# sma-test-20190912a.net
KiCad netlist of a schematic drawn in EAGLE
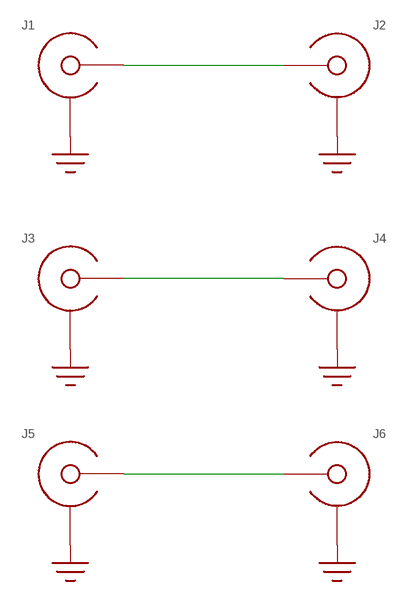
[diagram p0: schematic, sheet 1]

(export (version "E")
  (design (tool "Eeschema 10.0.6"))
  (components
    (comp (ref "J1")
      (value "SMA-EDGE-LAUNCH4020N")
      (footprint "eagle-import:SMA_EDGE_LAUNCH_4L_4020_N")
      (libsource (lib "eagle-import") (part "SMA-EDGE-LAUNCH4020N"))
    )
    (comp (ref "J2")
      (value "SMA-EDGE-LAUNCH4020N1")
      (footprint "eagle-import:SMA_EDGE_LAUNCH_4L_4020_N1")
      (libsource (lib "eagle-import") (part "SMA-EDGE-LAUNCH4020N1"))
    )
    (comp (ref "J3")
      (value "SMA-EDGE-LAUNCH4020N2")
      (footprint "eagle-import:SMA_EDGE_LAUNCH_4L_4020_N2")
      (libsource (lib "eagle-import") (part "SMA-EDGE-LAUNCH4020N2"))
    )
    (comp (ref "J4")
      (value "SMA-EDGE-LAUNCH4020N3")
      (footprint "eagle-import:SMA_EDGE_LAUNCH_4L_4020_N3")
      (libsource (lib "eagle-import") (part "SMA-EDGE-LAUNCH4020N3"))
    )
    (comp (ref "J5")
      (value "SMA-EDGE-LAUNCH4020N4")
      (footprint "eagle-import:SMA_EDGE_LAUNCH_4L_4020_N4")
      (libsource (lib "eagle-import") (part "SMA-EDGE-LAUNCH4020N4"))
    )
    (comp (ref "J6")
      (value "SMA-EDGE-LAUNCH4L-4020-TAPER-FIXED")
      (footprint "eagle-import:SMA_EDGE_LAUNCH_4L_4020_TAPER_FIXED")
      (libsource (lib "eagle-import") (part "SMA-EDGE-LAUNCH4L-4020-TAPER-FIXED"))
    )
  )
  (nets
    (net (code "1") (name "GND") (class "Default")
      (node (ref "J1") (pin "BOTTOM_GND") (pinfunction "SHIELD_BOTTOM_GND") (pintype "bidirectional"))
      (node (ref "J1") (pin "GND@1") (pinfunction "SHIELD_GND@1") (pintype "bidirectional"))
      (node (ref "J1") (pin "GND@14") (pinfunction "SHIELD_GND@14") (pintype "bidirectional"))
      (node (ref "J1") (pin "GND@15") (pinfunction "SHIELD_GND@15") (pintype "bidirectional"))
      (node (ref "J1") (pin "GND@16") (pinfunction "SHIELD_GND@16") (pintype "bidirectional"))
      (node (ref "J1") (pin "GND@17") (pinfunction "SHIELD_GND@17") (pintype "bidirectional"))
      (node (ref "J1") (pin "GND@2") (pinfunction "SHIELD_GND@2") (pintype "bidirectional"))
      (node (ref "J1") (pin "GND@3") (pinfunction "SHIELD_GND@3") (pintype "bidirectional"))
      (node (ref "J1") (pin "GND@4") (pinfunction "SHIELD_GND@4") (pintype "bidirectional"))
      (node (ref "J1") (pin "GND@5") (pinfunction "SHIELD_GND@5") (pintype "bidirectional"))
      (node (ref "J1") (pin "GND@6") (pinfunction "SHIELD_GND@6") (pintype "bidirectional"))
      (node (ref "J1") (pin "GND@7") (pinfunction "SHIELD_GND@7") (pintype "bidirectional"))
      (node (ref "J1") (pin "GND@8") (pinfunction "SHIELD_GND@8") (pintype "bidirectional"))
      (node (ref "J1") (pin "GND_PAD1") (pinfunction "SHIELD_GND_PAD1") (pintype "bidirectional"))
      (node (ref "J1") (pin "GND_PAD2") (pinfunction "SHIELD_GND_PAD2") (pintype "bidirectional"))
      (node (ref "J1") (pin "P$1") (pinfunction "SHIELD_P$1") (pintype "bidirectional"))
      (node (ref "J1") (pin "P$2") (pinfunction "SHIELD_P$2") (pintype "bidirectional"))
      (node (ref "J2") (pin "BOTTOM_GND") (pinfunction "SHIELD_BOTTOM_GND") (pintype "bidirectional"))
      (node (ref "J2") (pin "GND@1") (pinfunction "SHIELD_GND@1") (pintype "bidirectional"))
      (node (ref "J2") (pin "GND@14") (pinfunction "SHIELD_GND@14") (pintype "bidirectional"))
      (node (ref "J2") (pin "GND@15") (pinfunction "SHIELD_GND@15") (pintype "bidirectional"))
      (node (ref "J2") (pin "GND@16") (pinfunction "SHIELD_GND@16") (pintype "bidirectional"))
      (node (ref "J2") (pin "GND@17") (pinfunction "SHIELD_GND@17") (pintype "bidirectional"))
      (node (ref "J2") (pin "GND@2") (pinfunction "SHIELD_GND@2") (pintype "bidirectional"))
      (node (ref "J2") (pin "GND@3") (pinfunction "SHIELD_GND@3") (pintype "bidirectional"))
      (node (ref "J2") (pin "GND@4") (pinfunction "SHIELD_GND@4") (pintype "bidirectional"))
      (node (ref "J2") (pin "GND@5") (pinfunction "SHIELD_GND@5") (pintype "bidirectional"))
      (node (ref "J2") (pin "GND@6") (pinfunction "SHIELD_GND@6") (pintype "bidirectional"))
      (node (ref "J2") (pin "GND@7") (pinfunction "SHIELD_GND@7") (pintype "bidirectional"))
      (node (ref "J2") (pin "GND@8") (pinfunction "SHIELD_GND@8") (pintype "bidirectional"))
      (node (ref "J2") (pin "GND_PAD1") (pinfunction "SHIELD_GND_PAD1") (pintype "bidirectional"))
      (node (ref "J2") (pin "GND_PAD2") (pinfunction "SHIELD_GND_PAD2") (pintype "bidirectional"))
      (node (ref "J2") (pin "P$1") (pinfunction "SHIELD_P$1") (pintype "bidirectional"))
      (node (ref "J2") (pin "P$2") (pinfunction "SHIELD_P$2") (pintype "bidirectional"))
      (node (ref "J2") (pin "P$3") (pinfunction "SHIELD_P$3") (pintype "bidirectional"))
      (node (ref "J2") (pin "P$4") (pinfunction "SHIELD_P$4") (pintype "bidirectional"))
      (node (ref "J2") (pin "P$5") (pinfunction "SHIELD_P$5") (pintype "bidirectional"))
      (node (ref "J3") (pin "BOTTOM_GND") (pinfunction "SHIELD_BOTTOM_GND") (pintype "bidirectional"))
      (node (ref "J3") (pin "GND@1") (pinfunction "SHIELD_GND@1") (pintype "bidirectional"))
      (node (ref "J3") (pin "GND@14") (pinfunction "SHIELD_GND@14") (pintype "bidirectional"))
      (node (ref "J3") (pin "GND@15") (pinfunction "SHIELD_GND@15") (pintype "bidirectional"))
      (node (ref "J3") (pin "GND@16") (pinfunction "SHIELD_GND@16") (pintype "bidirectional"))
      (node (ref "J3") (pin "GND@17") (pinfunction "SHIELD_GND@17") (pintype "bidirectional"))
      (node (ref "J3") (pin "GND@2") (pinfunction "SHIELD_GND@2") (pintype "bidirectional"))
      (node (ref "J3") (pin "GND@3") (pinfunction "SHIELD_GND@3") (pintype "bidirectional"))
      (node (ref "J3") (pin "GND@4") (pinfunction "SHIELD_GND@4") (pintype "bidirectional"))
      (node (ref "J3") (pin "GND@5") (pinfunction "SHIELD_GND@5") (pintype "bidirectional"))
      (node (ref "J3") (pin "GND@6") (pinfunction "SHIELD_GND@6") (pintype "bidirectional"))
      (node (ref "J3") (pin "GND@7") (pinfunction "SHIELD_GND@7") (pintype "bidirectional"))
      (node (ref "J3") (pin "GND@8") (pinfunction "SHIELD_GND@8") (pintype "bidirectional"))
      (node (ref "J3") (pin "GND_PAD1") (pinfunction "SHIELD_GND_PAD1") (pintype "bidirectional"))
      (node (ref "J3") (pin "GND_PAD2") (pinfunction "SHIELD_GND_PAD2") (pintype "bidirectional"))
      (node (ref "J3") (pin "P$1") (pinfunction "SHIELD_P$1") (pintype "bidirectional"))
      (node (ref "J3") (pin "P$2") (pinfunction "SHIELD_P$2") (pintype "bidirectional"))
      (node (ref "J4") (pin "BOTTOM_GND") (pinfunction "SHIELD_BOTTOM_GND") (pintype "bidirectional"))
      (node (ref "J4") (pin "GND@1") (pinfunction "SHIELD_GND@1") (pintype "bidirectional"))
      (node (ref "J4") (pin "GND@14") (pinfunction "SHIELD_GND@14") (pintype "bidirectional"))
      (node (ref "J4") (pin "GND@15") (pinfunction "SHIELD_GND@15") (pintype "bidirectional"))
      (node (ref "J4") (pin "GND@16") (pinfunction "SHIELD_GND@16") (pintype "bidirectional"))
      (node (ref "J4") (pin "GND@17") (pinfunction "SHIELD_GND@17") (pintype "bidirectional"))
      (node (ref "J4") (pin "GND@2") (pinfunction "SHIELD_GND@2") (pintype "bidirectional"))
      (node (ref "J4") (pin "GND@3") (pinfunction "SHIELD_GND@3") (pintype "bidirectional"))
      (node (ref "J4") (pin "GND@4") (pinfunction "SHIELD_GND@4") (pintype "bidirectional"))
      (node (ref "J4") (pin "GND@5") (pinfunction "SHIELD_GND@5") (pintype "bidirectional"))
      (node (ref "J4") (pin "GND@6") (pinfunction "SHIELD_GND@6") (pintype "bidirectional"))
      (node (ref "J4") (pin "GND@7") (pinfunction "SHIELD_GND@7") (pintype "bidirectional"))
      (node (ref "J4") (pin "GND@8") (pinfunction "SHIELD_GND@8") (pintype "bidirectional"))
      (node (ref "J4") (pin "GND_PAD1") (pinfunction "SHIELD_GND_PAD1") (pintype "bidirectional"))
      (node (ref "J4") (pin "GND_PAD2") (pinfunction "SHIELD_GND_PAD2") (pintype "bidirectional"))
      (node (ref "J4") (pin "P$1") (pinfunction "SHIELD_P$1") (pintype "bidirectional"))
      (node (ref "J4") (pin "P$2") (pinfunction "SHIELD_P$2") (pintype "bidirectional"))
      (node (ref "J4") (pin "P$3") (pinfunction "SHIELD_P$3") (pintype "bidirectional"))
      (node (ref "J4") (pin "P$4") (pinfunction "SHIELD_P$4") (pintype "bidirectional"))
      (node (ref "J5") (pin "BOTTOM_GND") (pinfunction "SHIELD_BOTTOM_GND") (pintype "bidirectional"))
      (node (ref "J5") (pin "GND@1") (pinfunction "SHIELD_GND@1") (pintype "bidirectional"))
      (node (ref "J5") (pin "GND@10") (pinfunction "SHIELD_GND@10") (pintype "bidirectional"))
      (node (ref "J5") (pin "GND@14") (pinfunction "SHIELD_GND@14") (pintype "bidirectional"))
      (node (ref "J5") (pin "GND@15") (pinfunction "SHIELD_GND@15") (pintype "bidirectional"))
      (node (ref "J5") (pin "GND@16") (pinfunction "SHIELD_GND@16") (pintype "bidirectional"))
      (node (ref "J5") (pin "GND@17") (pinfunction "SHIELD_GND@17") (pintype "bidirectional"))
      (node (ref "J5") (pin "GND@2") (pinfunction "SHIELD_GND@2") (pintype "bidirectional"))
      (node (ref "J5") (pin "GND@3") (pinfunction "SHIELD_GND@3") (pintype "bidirectional"))
      (node (ref "J5") (pin "GND@4") (pinfunction "SHIELD_GND@4") (pintype "bidirectional"))
      (node (ref "J5") (pin "GND@5") (pinfunction "SHIELD_GND@5") (pintype "bidirectional"))
      (node (ref "J5") (pin "GND@6") (pinfunction "SHIELD_GND@6") (pintype "bidirectional"))
      (node (ref "J5") (pin "GND@7") (pinfunction "SHIELD_GND@7") (pintype "bidirectional"))
      (node (ref "J5") (pin "GND@8") (pinfunction "SHIELD_GND@8") (pintype "bidirectional"))
      (node (ref "J5") (pin "GND@9") (pinfunction "SHIELD_GND@9") (pintype "bidirectional"))
      (node (ref "J5") (pin "GND_PAD1") (pinfunction "SHIELD_GND_PAD1") (pintype "bidirectional"))
      (node (ref "J5") (pin "GND_PAD2") (pinfunction "SHIELD_GND_PAD2") (pintype "bidirectional"))
      (node (ref "J5") (pin "P$1") (pinfunction "SHIELD_P$1") (pintype "bidirectional"))
      (node (ref "J5") (pin "P$2") (pinfunction "SHIELD_P$2") (pintype "bidirectional"))
      (node (ref "J5") (pin "P$3") (pinfunction "SHIELD_P$3") (pintype "bidirectional"))
      (node (ref "J5") (pin "P$4") (pinfunction "SHIELD_P$4") (pintype "bidirectional"))
      (node (ref "J5") (pin "P$5") (pinfunction "SHIELD_P$5") (pintype "bidirectional"))
      (node (ref "J6") (pin "BOTTOM_GND") (pinfunction "SHIELD_BOTTOM_GND") (pintype "bidirectional"))
      (node (ref "J6") (pin "GND@1") (pinfunction "SHIELD_GND@1") (pintype "bidirectional"))
      (node (ref "J6") (pin "GND@14") (pinfunction "SHIELD_GND@14") (pintype "bidirectional"))
      (node (ref "J6") (pin "GND@15") (pinfunction "SHIELD_GND@15") (pintype "bidirectional"))
      (node (ref "J6") (pin "GND@16") (pinfunction "SHIELD_GND@16") (pintype "bidirectional"))
      (node (ref "J6") (pin "GND@17") (pinfunction "SHIELD_GND@17") (pintype "bidirectional"))
      (node (ref "J6") (pin "GND@2") (pinfunction "SHIELD_GND@2") (pintype "bidirectional"))
      (node (ref "J6") (pin "GND@3") (pinfunction "SHIELD_GND@3") (pintype "bidirectional"))
      (node (ref "J6") (pin "GND@4") (pinfunction "SHIELD_GND@4") (pintype "bidirectional"))
      (node (ref "J6") (pin "GND@5") (pinfunction "SHIELD_GND@5") (pintype "bidirectional"))
      (node (ref "J6") (pin "GND@6") (pinfunction "SHIELD_GND@6") (pintype "bidirectional"))
      (node (ref "J6") (pin "GND@7") (pinfunction "SHIELD_GND@7") (pintype "bidirectional"))
      (node (ref "J6") (pin "GND@8") (pinfunction "SHIELD_GND@8") (pintype "bidirectional"))
      (node (ref "J6") (pin "GND_PAD1") (pinfunction "SHIELD_GND_PAD1") (pintype "bidirectional"))
      (node (ref "J6") (pin "GND_PAD2") (pinfunction "SHIELD_GND_PAD2") (pintype "bidirectional"))
      (node (ref "J6") (pin "P$1") (pinfunction "SHIELD_P$1") (pintype "bidirectional"))
      (node (ref "J6") (pin "P$2") (pinfunction "SHIELD_P$2") (pintype "bidirectional"))
    )
    (net (code "2") (name "Net-(J1-CENTER-PadCENTER@1)") (class "Default")
      (node (ref "J1") (pin "CENTER@1") (pinfunction "CENTER_CENTER@1") (pintype "bidirectional"))
      (node (ref "J1") (pin "CENTER@2") (pinfunction "CENTER_CENTER@2") (pintype "bidirectional"))
      (node (ref "J2") (pin "CENTER@1") (pinfunction "CENTER_CENTER@1") (pintype "bidirectional"))
      (node (ref "J2") (pin "CENTER@2") (pinfunction "CENTER_CENTER@2") (pintype "bidirectional"))
    )
    (net (code "3") (name "Net-(J3-CENTER-PadCENTER@1)") (class "Default")
      (node (ref "J3") (pin "CENTER@1") (pinfunction "CENTER_CENTER@1") (pintype "bidirectional"))
      (node (ref "J3") (pin "CENTER@2") (pinfunction "CENTER_CENTER@2") (pintype "bidirectional"))
      (node (ref "J4") (pin "CENTER@1") (pinfunction "CENTER_CENTER@1") (pintype "bidirectional"))
      (node (ref "J4") (pin "CENTER@2") (pinfunction "CENTER_CENTER@2") (pintype "bidirectional"))
    )
    (net (code "4") (name "Net-(J5-CENTER-PadCENTER@1)") (class "Default")
      (node (ref "J5") (pin "CENTER@1") (pinfunction "CENTER_CENTER@1") (pintype "bidirectional"))
      (node (ref "J5") (pin "CENTER@2") (pinfunction "CENTER_CENTER@2") (pintype "bidirectional"))
      (node (ref "J6") (pin "CENTER@1") (pinfunction "CENTER_CENTER@1") (pintype "bidirectional"))
      (node (ref "J6") (pin "P$3") (pinfunction "CENTER_P$3") (pintype "bidirectional"))
    )
  )
)
